# Buck_and_LDO.net
KiCad netlist of a schematic drawn in Altium Designer
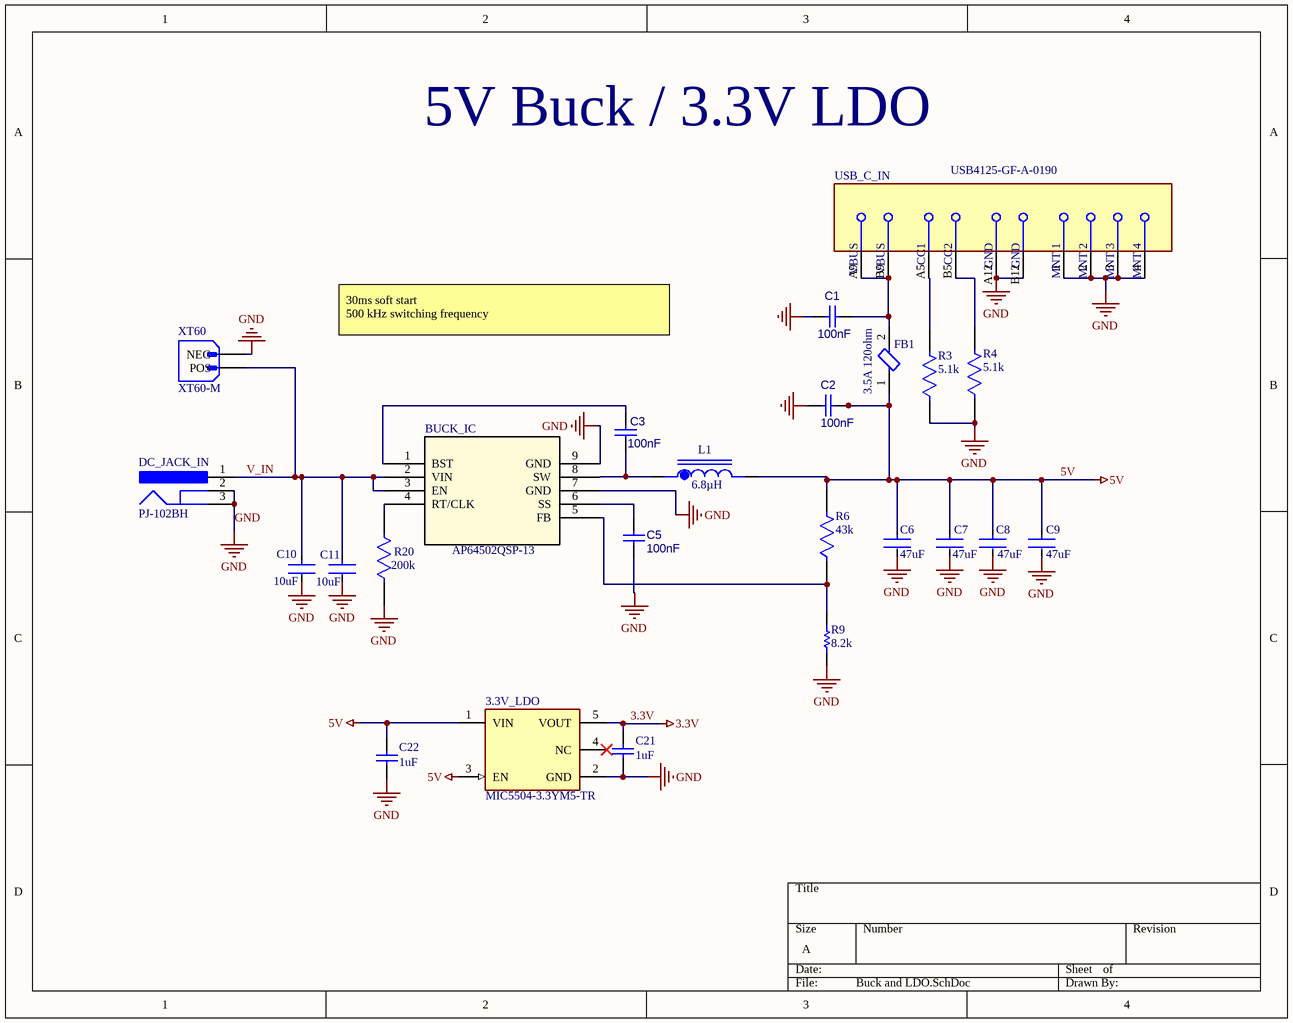
[diagram p0: Buck and LDO.SchDoc]

(export (version "E")
  (design (tool "Eeschema 10.0.6"))
  (components
    (comp (ref "3.3V_LDO")
      (value "MIC5504-3.3YM5-TR")
      (footprint "FP-SOT23-5LD-PL-1-MFG")
      (description "IC REG LINEAR 3.3V 300MA SOT23-5")
      (libsource (lib "Altium Content Vault") (part "96048095611b4a9579e1e315950d302"))
    )
    (comp (ref "BUCK_IC")
      (value "AP64502QSP-13")
      (footprint "SO-8EP_DIO")
      (description "Description")
      (fields (field (name "COPYRIGHT") "Copyright (C) 2025 Ultra Librarian. All rights reserved."))
      (libsource (lib "AP64502QSP-13") (part "AP64502QSP-13"))
    )
    (comp (ref "C1")
      (value "100nF")
      (footprint "CAPC2013X95X50LL10T25")
      (description "Capacitor 100 nF +/-10% 50 V 0805")
      (fields (field (name "TOLERANCE") "10%"))
      (libsource (lib "gugan Sivakumar") (part "CAP-NP-2"))
    )
    (comp (ref "C2")
      (value "100nF")
      (footprint "CAPC2013X95X50LL10T25")
      (description "Capacitor 100 nF +/-10% 50 V 0805")
      (fields (field (name "TOLERANCE") "10%"))
      (libsource (lib "gugan Sivakumar") (part "CAP-NP-2"))
    )
    (comp (ref "C3")
      (value "100nF")
      (footprint "CAPC2013X95X50LL10T25")
      (description "Capacitor 100 nF +/-10% 50 V 0805")
      (fields (field (name "TOLERANCE") "10%"))
      (libsource (lib "gugan Sivakumar") (part "CAP-NP-2"))
    )
    (comp (ref "C5")
      (value "100nF")
      (footprint "CAPC2013X95X50LL10T25")
      (description "Capacitor 100 nF +/-10% 50 V 0805")
      (fields (field (name "TOLERANCE") "10%"))
      (libsource (lib "gugan Sivakumar") (part "CAP-NP-2"))
    )
    (comp (ref "C6")
      (value "47uF")
      (footprint "FP-GRM31C-0_2-e0_3_0_8-IPC_C")
      (description "Chip Multilayer Ceramic Capacitors for General Purpose, 1206, 47uF, X5R, 15%, 20%, 10V")
      (fields (field (name "TOLERANCE") "20%") (field (name "VOLTAGE") "10V"))
      (libsource (lib "Altium Content Vault") (part "02cd4be3c70576c341d710602a673aa"))
    )
    (comp (ref "C7")
      (value "47uF")
      (footprint "FP-GRM31C-0_2-e0_3_0_8-IPC_C")
      (description "Chip Multilayer Ceramic Capacitors for General Purpose, 1206, 47uF, X5R, 15%, 20%, 10V")
      (fields (field (name "TOLERANCE") "20%") (field (name "VOLTAGE") "10V"))
      (libsource (lib "Altium Content Vault") (part "02cd4be3c70576c341d710602a673aa"))
    )
    (comp (ref "C8")
      (value "47uF")
      (footprint "FP-GRM31C-0_2-e0_3_0_8-IPC_C")
      (description "Chip Multilayer Ceramic Capacitors for General Purpose, 1206, 47uF, X5R, 15%, 20%, 10V")
      (fields (field (name "TOLERANCE") "20%") (field (name "VOLTAGE") "10V"))
      (libsource (lib "Altium Content Vault") (part "02cd4be3c70576c341d710602a673aa"))
    )
    (comp (ref "C9")
      (value "47uF")
      (footprint "FP-GRM31C-0_2-e0_3_0_8-IPC_C")
      (description "Chip Multilayer Ceramic Capacitors for General Purpose, 1206, 47uF, X5R, 15%, 20%, 10V")
      (fields (field (name "TOLERANCE") "20%") (field (name "VOLTAGE") "10V"))
      (libsource (lib "Altium Content Vault") (part "02cd4be3c70576c341d710602a673aa"))
    )
    (comp (ref "C10")
      (value "10uF")
      (footprint "FP-CL31-IPC_C")
      (description "CAP CER 10UF 50V X5R 1206")
      (fields (field (name "TOLERANCE") "10%") (field (name "MANUFACTURER") "Samsung"))
      (libsource (lib "Altium Content Vault") (part "11868f565c42a9108669ba33697ecf6"))
    )
    (comp (ref "C11")
      (value "10uF")
      (footprint "FP-CL31-IPC_C")
      (description "CAP CER 10UF 50V X5R 1206")
      (fields (field (name "TOLERANCE") "10%") (field (name "MANUFACTURER") "Samsung"))
      (libsource (lib "Altium Content Vault") (part "11868f565c42a9108669ba33697ecf6"))
    )
    (comp (ref "C21")
      (value "1uF")
      (footprint "CAPC3216X180X50ML20T25")
      (description "Chip Capacitor, 1 uF, +/- 10%, 25 V, -55 to 125 degC, 1206 (3216 Metric), RoHS, Tape and Reel")
      (fields (field (name "MANUFACTURER") "Kemet") (field (name "TOLERANCE") "10%"))
      (libsource (lib "Altium Content Vault") (part "CAP-NP-2"))
    )
    (comp (ref "C22")
      (value "1uF")
      (footprint "CAPC3216X180X50ML20T25")
      (description "Chip Capacitor, 1 uF, +/- 10%, 25 V, -55 to 125 degC, 1206 (3216 Metric), RoHS, Tape and Reel")
      (fields (field (name "MANUFACTURER") "Kemet") (field (name "TOLERANCE") "10%"))
      (libsource (lib "Altium Content Vault") (part "CAP-NP-2"))
    )
    (comp (ref "DC_JACK_IN")
      (value "PJ-102BH")
      (footprint "CUI-PJ-102BH_V")
      (fields (field (name "MANUFACTURER") "CUIInc."))
      (libsource (lib "Altium Content Vault") (part "JACK-2CD3-RN"))
    )
    (comp (ref "FB1")
      (value "3.5A 120ohm")
      (footprint "FP-BLM31-0_2-t1_1-MFG")
      (description "BLM31PG121SN1L Chip Ferrite Bead Array, 1206, 120Ω @ 100MHz, 0.02Ω, 25%, 3.5A")
      (fields (field (name "TOLERANCE") "25%"))
      (libsource (lib "Altium Content Vault") (part "5f30dd21d616792df468990f7003faa"))
    )
    (comp (ref "L1")
      (value "6.8µH")
      (footprint "IND_MGAH06036R8M-10")
      (description "6.8 ÂµH Shielded Molded Inductor 5 A 50mOhm Max Nonstandard")
      (fields (field (name "MP") "MGAH06036R8M-10") (field (name "MF") "Laird-Signal Integrity Products"))
      (libsource (lib "gugan Sivakumar") (part "MGAH06036R8M-10"))
    )
    (comp (ref "R3")
      (value "5.1k")
      (footprint "FP-MCT0603-IPC_B")
      (description "MCT06030D5101BP500 RES SMD 5100 OHM 1% 1/8W 0603")
      (fields (field (name "TOLERANCE") "0.1%"))
      (libsource (lib "Altium Content Vault") (part "1029c3af85768c4190bb7ad29bc67b5"))
    )
    (comp (ref "R4")
      (value "5.1k")
      (footprint "FP-MCT0603-IPC_B")
      (description "MCT06030D5101BP500 RES SMD 5100 OHM 1% 1/8W 0603")
      (fields (field (name "TOLERANCE") "0.1%"))
      (libsource (lib "Altium Content Vault") (part "1029c3af85768c4190bb7ad29bc67b5"))
    )
    (comp (ref "R6")
      (value "43k")
      (footprint "FP-MCU0805-IPC_C")
      (description "MCU08050C4302FP500 RES 1.05K OHM 0.5% 1/5W 0805")
      (fields (field (name "TOLERANCE") "1%"))
      (libsource (lib "Altium Content Vault") (part "1029c3af85768c4190bb7ad29bc67b5"))
    )
    (comp (ref "R9")
      (value "8.2k")
      (footprint "RESC0805(2012)_N")
      (description "8K2 0.125W 1% 0805 (2012 Metric)  SMD")
      (fields (field (name "POWER") "0.125 W") (field (name "TOLERANCE") "1 %"))
      (libsource (lib "Altium Content Vault") (part "RES"))
    )
    (comp (ref "R20")
      (value "200k")
      (footprint "FP-CRCW0603-HPe3-MFG")
      (description "RES Thick Film, 200kΩ, 1%, 0.33W, 100ppm/°C, 0603")
      (fields (field (name "TOLERANCE") "1%"))
      (libsource (lib "Altium Content Vault") (part "1029c3af85768c4190bb7ad29bc67b5"))
    )
    (comp (ref "USB_C_IN")
      (value "USB4125-GF-A-0190")
      (footprint "FP-USB4125-GF-A-0190-MFG")
      (description "CONN RCPT TYPE C 6P SMD RA")
      (libsource (lib "Altium Content Vault") (part "a055484d46e58b234844902c9fd883a"))
    )
    (comp (ref "XT60")
      (value "XT60-M")
      (footprint "AMASS_XT60-M")
      (description "Plug; DC supply; XT60; male; PIN: 2; for cable; soldered; 30A; 500V")
      (fields (field (name "MF") "AMASS"))
      (libsource (lib "gugan Sivakumar") (part "XT60-M"))
    )
  )
  (nets
    (net (code "1") (name "/V_IN") (class "Default")
      (node (ref "BUCK_IC") (pin "2") (pinfunction "VIN_2") (pintype "passive"))
      (node (ref "BUCK_IC") (pin "3") (pinfunction "EN_3") (pintype "passive"))
      (node (ref "C10") (pin "1") (pinfunction "1_1") (pintype "passive"))
      (node (ref "C11") (pin "1") (pinfunction "1_1") (pintype "passive"))
      (node (ref "DC_JACK_IN") (pin "1") (pinfunction "1_1") (pintype "passive"))
      (node (ref "XT60") (pin "P") (pinfunction "POS_P") (pintype "passive"))
    )
    (net (code "2") (name "3.3V") (class "Default")
      (node (ref "3.3V_LDO") (pin "5") (pinfunction "VOUT_5") (pintype "power_in"))
      (node (ref "C21") (pin "2") (pinfunction "2_2") (pintype "passive"))
    )
    (net (code "3") (name "5V") (class "Default")
      (node (ref "3.3V_LDO") (pin "1") (pinfunction "VIN_1") (pintype "power_in"))
      (node (ref "3.3V_LDO") (pin "3") (pinfunction "EN_3") (pintype "input"))
      (node (ref "C2") (pin "2") (pinfunction "2_2") (pintype "passive"))
      (node (ref "C22") (pin "2") (pinfunction "2_2") (pintype "passive"))
      (node (ref "C6") (pin "1") (pinfunction "1_1") (pintype "passive"))
      (node (ref "C7") (pin "1") (pinfunction "1_1") (pintype "passive"))
      (node (ref "C8") (pin "1") (pinfunction "1_1") (pintype "passive"))
      (node (ref "C9") (pin "1") (pinfunction "1_1") (pintype "passive"))
      (node (ref "FB1") (pin "1") (pinfunction "1_1") (pintype "passive"))
      (node (ref "L1") (pin "2") (pinfunction "2_2") (pintype "passive"))
      (node (ref "R6") (pin "2") (pinfunction "2_2") (pintype "passive"))
    )
    (net (code "4") (name "GND") (class "Default")
      (node (ref "3.3V_LDO") (pin "2") (pinfunction "GND_2") (pintype "power_in"))
      (node (ref "BUCK_IC") (pin "7") (pinfunction "GND_7") (pintype "passive"))
      (node (ref "BUCK_IC") (pin "9") (pinfunction "GND_9") (pintype "passive"))
      (node (ref "C1") (pin "1") (pinfunction "1_1") (pintype "passive"))
      (node (ref "C10") (pin "2") (pinfunction "2_2") (pintype "passive"))
      (node (ref "C11") (pin "2") (pinfunction "2_2") (pintype "passive"))
      (node (ref "C2") (pin "1") (pinfunction "1_1") (pintype "passive"))
      (node (ref "C21") (pin "1") (pinfunction "1_1") (pintype "passive"))
      (node (ref "C22") (pin "1") (pinfunction "1_1") (pintype "passive"))
      (node (ref "C5") (pin "1") (pinfunction "1_1") (pintype "passive"))
      (node (ref "C6") (pin "2") (pinfunction "2_2") (pintype "passive"))
      (node (ref "C7") (pin "2") (pinfunction "2_2") (pintype "passive"))
      (node (ref "C8") (pin "2") (pinfunction "2_2") (pintype "passive"))
      (node (ref "C9") (pin "2") (pinfunction "2_2") (pintype "passive"))
      (node (ref "DC_JACK_IN") (pin "2") (pinfunction "2_2") (pintype "passive"))
      (node (ref "DC_JACK_IN") (pin "3") (pinfunction "3_3") (pintype "passive"))
      (node (ref "R20") (pin "1") (pinfunction "1_1") (pintype "passive"))
      (node (ref "R3") (pin "1") (pinfunction "1_1") (pintype "passive"))
      (node (ref "R4") (pin "1") (pinfunction "1_1") (pintype "passive"))
      (node (ref "R9") (pin "1") (pinfunction "1_1") (pintype "passive"))
      (node (ref "USB_C_IN") (pin "1") (pinfunction "MNT_1_1") (pintype "passive"))
      (node (ref "USB_C_IN") (pin "2") (pinfunction "MNT_2_2") (pintype "passive"))
      (node (ref "USB_C_IN") (pin "3") (pinfunction "MNT_3_3") (pintype "passive"))
      (node (ref "USB_C_IN") (pin "4") (pinfunction "MNT_4_4") (pintype "passive"))
      (node (ref "USB_C_IN") (pin "A12") (pinfunction "GND_A12") (pintype "passive"))
      (node (ref "USB_C_IN") (pin "B12") (pinfunction "GND_B12") (pintype "passive"))
      (node (ref "XT60") (pin "N") (pinfunction "NEG_N") (pintype "passive"))
    )
    (net (code "5") (name "Net-(BUCK_IC-BST)") (class "Default")
      (node (ref "BUCK_IC") (pin "1") (pinfunction "BST_1") (pintype "passive"))
      (node (ref "C3") (pin "2") (pinfunction "2_2") (pintype "passive"))
    )
    (net (code "6") (name "Net-(BUCK_IC-FB)") (class "Default")
      (node (ref "BUCK_IC") (pin "5") (pinfunction "FB_5") (pintype "passive"))
      (node (ref "R6") (pin "1") (pinfunction "1_1") (pintype "passive"))
      (node (ref "R9") (pin "2") (pinfunction "2_2") (pintype "passive"))
    )
    (net (code "7") (name "Net-(BUCK_IC-RT{slash}CLK)") (class "Default")
      (node (ref "BUCK_IC") (pin "4") (pinfunction "RT/CLK_4") (pintype "passive"))
      (node (ref "R20") (pin "2") (pinfunction "2_2") (pintype "passive"))
    )
    (net (code "8") (name "Net-(BUCK_IC-SS)") (class "Default")
      (node (ref "BUCK_IC") (pin "6") (pinfunction "SS_6") (pintype "passive"))
      (node (ref "C5") (pin "2") (pinfunction "2_2") (pintype "passive"))
    )
    (net (code "9") (name "Net-(BUCK_IC-SW)") (class "Default")
      (node (ref "BUCK_IC") (pin "8") (pinfunction "SW_8") (pintype "passive"))
      (node (ref "C3") (pin "1") (pinfunction "1_1") (pintype "passive"))
      (node (ref "L1") (pin "1") (pinfunction "1_1") (pintype "passive"))
    )
    (net (code "10") (name "Net-(C1-Pad2)") (class "Default")
      (node (ref "C1") (pin "2") (pinfunction "2_2") (pintype "passive"))
      (node (ref "FB1") (pin "2") (pinfunction "2_2") (pintype "passive"))
      (node (ref "USB_C_IN") (pin "A9") (pinfunction "VBUS_A9") (pintype "passive"))
      (node (ref "USB_C_IN") (pin "B9") (pinfunction "VBUS_B9") (pintype "passive"))
    )
    (net (code "11") (name "Net-(USB_C_IN-CC1)") (class "Default")
      (node (ref "R3") (pin "2") (pinfunction "2_2") (pintype "passive"))
      (node (ref "USB_C_IN") (pin "A5") (pinfunction "CC1_A5") (pintype "passive"))
    )
    (net (code "12") (name "Net-(USB_C_IN-CC2)") (class "Default")
      (node (ref "R4") (pin "2") (pinfunction "2_2") (pintype "passive"))
      (node (ref "USB_C_IN") (pin "B5") (pinfunction "CC2_B5") (pintype "passive"))
    )
    (net (code "13") (name "unconnected-(3.3V_LDO-NC-Pad4)") (class "Default")
      (node (ref "3.3V_LDO") (pin "4") (pinfunction "NC_4") (pintype "passive+no_connect"))
    )
  )
)
